# Universal_Register_4Bit.net
KiCad netlist of a schematic drawn in Altium Designer
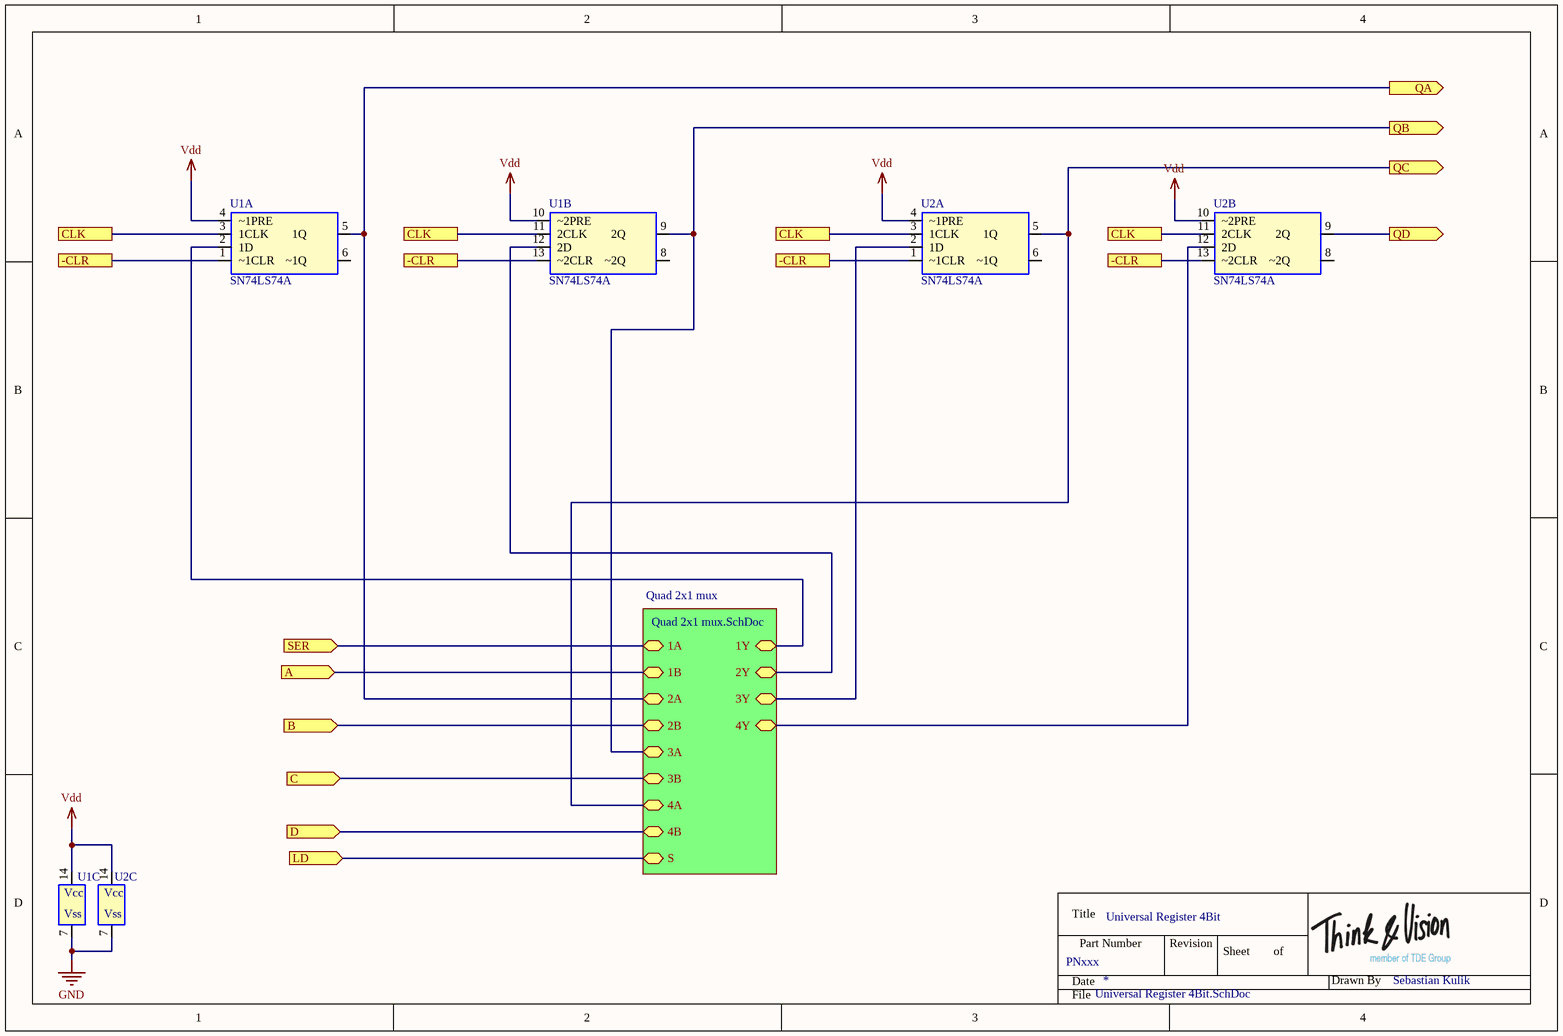
[diagram p0: Universal Register 4Bit.SchDoc]

(export (version "E")
  (design (tool "Eeschema 10.0.6"))
  (components
    (comp (ref "U1")
      (value "SN74LS74A")
      (footprint "DIP-14")
      (description "Flip-Flop Dual, TTL")
      (fields (field (name "MANUFACTURER") "TI") (field (name "PUBLISHER") "Sebastian Kulik"))
      (libsource (lib "ICs") (part "SN74LS74A"))
    )
    (comp (ref "U2")
      (value "SN74LS74A")
      (footprint "DIP-14")
      (description "Flip-Flop Dual, TTL")
      (fields (field (name "MANUFACTURER") "TI") (field (name "PUBLISHER") "Sebastian Kulik"))
      (libsource (lib "ICs") (part "SN74LS74A"))
    )
  )
  (nets
    (net (code "1") (name "/-CLR") (class "Default")
      (node (ref "U1") (pin "1") (pinfunction "~1CLR_1") (pintype "passive"))
      (node (ref "U1") (pin "13") (pinfunction "~2CLR_13") (pintype "passive"))
      (node (ref "U2") (pin "1") (pinfunction "~1CLR_1") (pintype "passive"))
      (node (ref "U2") (pin "13") (pinfunction "~2CLR_13") (pintype "passive"))
    )
    (net (code "2") (name "/1Y") (class "Default")
      (node (ref "U1") (pin "2") (pinfunction "1D_2") (pintype "passive"))
    )
    (net (code "3") (name "/2Y") (class "Default")
      (node (ref "U1") (pin "12") (pinfunction "2D_12") (pintype "passive"))
    )
    (net (code "4") (name "/3Y") (class "Default")
      (node (ref "U2") (pin "2") (pinfunction "1D_2") (pintype "passive"))
    )
    (net (code "5") (name "/4Y") (class "Default")
      (node (ref "U2") (pin "12") (pinfunction "2D_12") (pintype "passive"))
    )
    (net (code "9") (name "/CLK") (class "Default")
      (node (ref "U1") (pin "11") (pinfunction "2CLK_11") (pintype "passive"))
      (node (ref "U1") (pin "3") (pinfunction "1CLK_3") (pintype "passive"))
      (node (ref "U2") (pin "11") (pinfunction "2CLK_11") (pintype "passive"))
      (node (ref "U2") (pin "3") (pinfunction "1CLK_3") (pintype "passive"))
    )
    (net (code "12") (name "/QA") (class "Default")
      (node (ref "U1") (pin "5") (pinfunction "1Q_5") (pintype "passive"))
    )
    (net (code "13") (name "/QB") (class "Default")
      (node (ref "U1") (pin "9") (pinfunction "2Q_9") (pintype "passive"))
    )
    (net (code "14") (name "/QC") (class "Default")
      (node (ref "U2") (pin "5") (pinfunction "1Q_5") (pintype "passive"))
    )
    (net (code "15") (name "/QD") (class "Default")
      (node (ref "U2") (pin "9") (pinfunction "2Q_9") (pintype "passive"))
    )
    (net (code "17") (name "GND") (class "Default")
      (node (ref "U1") (pin "7") (pinfunction "Vss_7") (pintype "passive"))
      (node (ref "U2") (pin "7") (pinfunction "Vss_7") (pintype "passive"))
    )
    (net (code "18") (name "Vdd") (class "Default")
      (node (ref "U1") (pin "10") (pinfunction "~2PRE_10") (pintype "passive"))
      (node (ref "U1") (pin "14") (pinfunction "Vcc_14") (pintype "passive"))
      (node (ref "U1") (pin "4") (pinfunction "~1PRE_4") (pintype "passive"))
      (node (ref "U2") (pin "10") (pinfunction "~2PRE_10") (pintype "passive"))
      (node (ref "U2") (pin "14") (pinfunction "Vcc_14") (pintype "passive"))
      (node (ref "U2") (pin "4") (pinfunction "~1PRE_4") (pintype "passive"))
    )
    (net (code "19") (name "unconnected-(U1A-~1Q-Pad6)") (class "Default")
      (node (ref "U1") (pin "6") (pinfunction "~1Q_6") (pintype "passive"))
    )
    (net (code "20") (name "unconnected-(U1B-~2Q-Pad8)") (class "Default")
      (node (ref "U1") (pin "8") (pinfunction "~2Q_8") (pintype "passive"))
    )
    (net (code "21") (name "unconnected-(U2A-~1Q-Pad6)") (class "Default")
      (node (ref "U2") (pin "6") (pinfunction "~1Q_6") (pintype "passive"))
    )
    (net (code "22") (name "unconnected-(U2B-~2Q-Pad8)") (class "Default")
      (node (ref "U2") (pin "8") (pinfunction "~2Q_8") (pintype "passive"))
    )
  )
)
